# Scheme.net
KiCad netlist of a schematic drawn in EAGLE
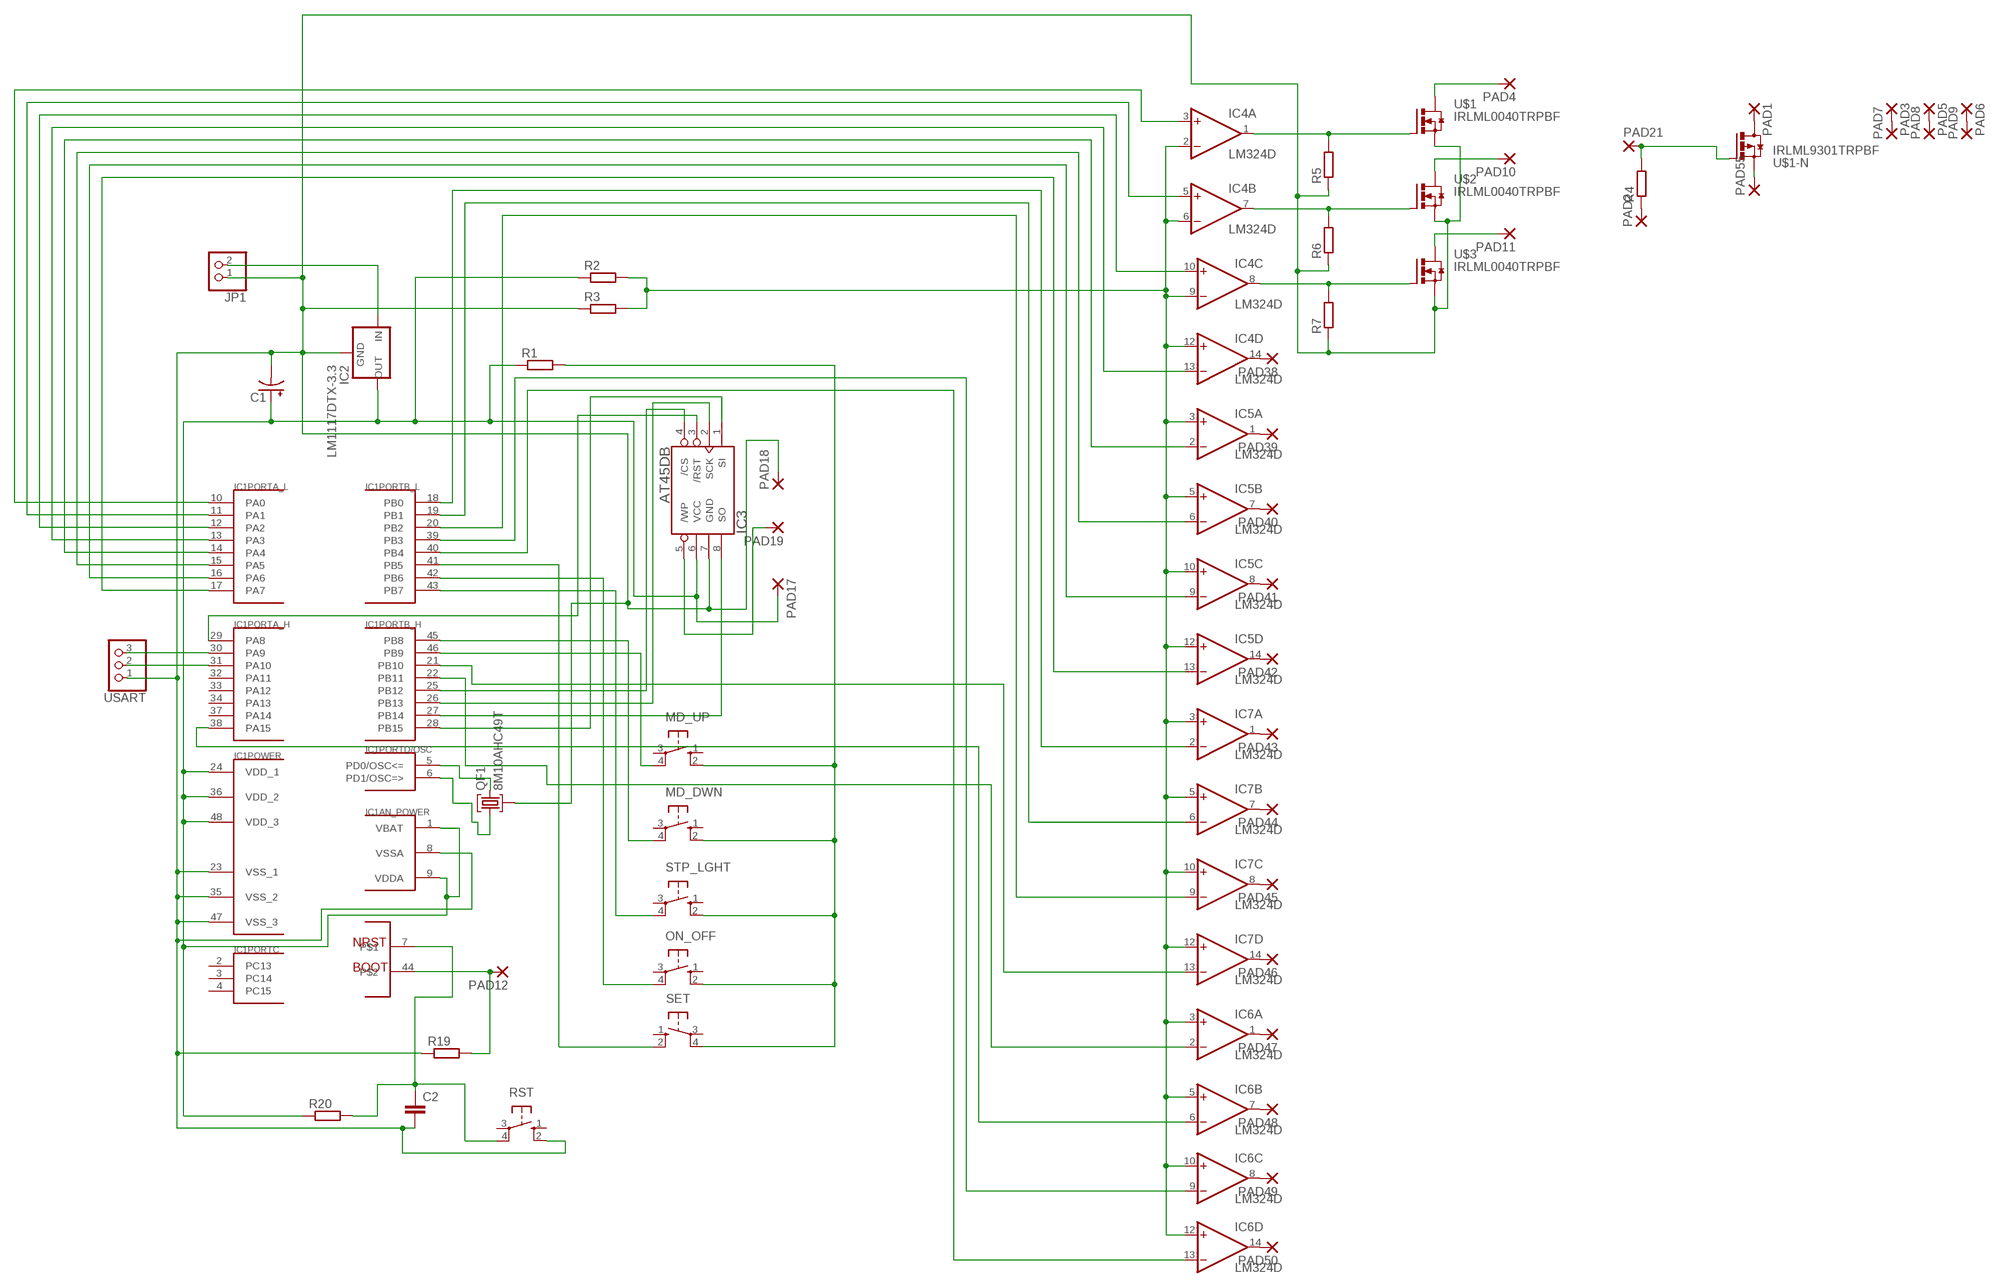
[diagram p0: schematic, sheet 1]

(export (version "E")
  (design (tool "Eeschema 10.0.6"))
  (components
    (comp (ref "C1")
      (value "CPOL-USSMCD")
      (footprint "eagle-import:SMC_D")
      (libsource (lib "eagle-import") (part "CPOL-USSMCD"))
    )
    (comp (ref "C2")
      (value "C-EUC0805")
      (footprint "eagle-import:C0805")
      (libsource (lib "eagle-import") (part "C-EUC0805"))
    )
    (comp (ref "IC1")
      (value "STM32F10XCXT6")
      (footprint "eagle-import:TQFP48")
      (libsource (lib "eagle-import") (part "STM32F10XCXT6"))
    )
    (comp (ref "IC2")
      (value "LM1117DTX-3.3")
      (footprint "eagle-import:TO252")
      (libsource (lib "eagle-import") (part "LM1117DTX-3.3"))
    )
    (comp (ref "IC3")
      (value "AT45DB-S")
      (footprint "eagle-import:SOIC8_208MIL")
      (libsource (lib "eagle-import") (part "AT45DB-S"))
    )
    (comp (ref "IC4")
      (value "LM324D")
      (footprint "eagle-import:SO14")
      (libsource (lib "eagle-import") (part "LM324D"))
    )
    (comp (ref "IC5")
      (value "LM324D")
      (footprint "eagle-import:SO14")
      (libsource (lib "eagle-import") (part "LM324D"))
    )
    (comp (ref "IC6")
      (value "LM324D")
      (footprint "eagle-import:SO14")
      (libsource (lib "eagle-import") (part "LM324D"))
    )
    (comp (ref "IC7")
      (value "LM324D")
      (footprint "eagle-import:SO14")
      (libsource (lib "eagle-import") (part "LM324D"))
    )
    (comp (ref "JP1")
      (value "PINHD-1X2")
      (footprint "eagle-import:1X02")
      (libsource (lib "eagle-import") (part "PINHD-1X2"))
    )
    (comp (ref "MD_DWN")
      (value "40-XX")
      (footprint "eagle-import:B3F-40XX")
      (fields (field (name "MF") "OMRON COMPONENTS USA") (field (name "MPN") "B3F-4000"))
      (libsource (lib "eagle-import") (part "40-XX"))
    )
    (comp (ref "MD_UP")
      (value "40-XX")
      (footprint "eagle-import:B3F-40XX")
      (fields (field (name "MF") "OMRON COMPONENTS USA") (field (name "MPN") "B3F-4000"))
      (libsource (lib "eagle-import") (part "40-XX"))
    )
    (comp (ref "ON_OFF")
      (value "40-XX")
      (footprint "eagle-import:B3F-40XX")
      (fields (field (name "MF") "OMRON COMPONENTS USA") (field (name "MPN") "B3F-4000"))
      (libsource (lib "eagle-import") (part "40-XX"))
    )
    (comp (ref "PAD1")
      (value "SMD2")
      (footprint "eagle-import:SMD1,27-2,54")
      (libsource (lib "eagle-import") (part "SMD2"))
    )
    (comp (ref "PAD2")
      (value "SMD2")
      (footprint "eagle-import:SMD1,27-2,54")
      (libsource (lib "eagle-import") (part "SMD2"))
    )
    (comp (ref "PAD3")
      (value "SMD2")
      (footprint "eagle-import:SMD1,27-2,54")
      (libsource (lib "eagle-import") (part "SMD2"))
    )
    (comp (ref "PAD4")
      (value "SMD2")
      (footprint "eagle-import:SMD1,27-2,54")
      (libsource (lib "eagle-import") (part "SMD2"))
    )
    (comp (ref "PAD5")
      (value "SMD2")
      (footprint "eagle-import:SMD1,27-2,54")
      (libsource (lib "eagle-import") (part "SMD2"))
    )
    (comp (ref "PAD6")
      (value "SMD2")
      (footprint "eagle-import:SMD1,27-2,54")
      (libsource (lib "eagle-import") (part "SMD2"))
    )
    (comp (ref "PAD7")
      (value "SMD2")
      (footprint "eagle-import:SMD1,27-2,54")
      (libsource (lib "eagle-import") (part "SMD2"))
    )
    (comp (ref "PAD8")
      (value "SMD2")
      (footprint "eagle-import:SMD1,27-2,54")
      (libsource (lib "eagle-import") (part "SMD2"))
    )
    (comp (ref "PAD9")
      (value "SMD2")
      (footprint "eagle-import:SMD1,27-2,54")
      (libsource (lib "eagle-import") (part "SMD2"))
    )
    (comp (ref "PAD10")
      (value "SMD2")
      (footprint "eagle-import:SMD1,27-2,54")
      (libsource (lib "eagle-import") (part "SMD2"))
    )
    (comp (ref "PAD11")
      (value "SMD2")
      (footprint "eagle-import:SMD1,27-2,54")
      (libsource (lib "eagle-import") (part "SMD2"))
    )
    (comp (ref "PAD12")
      (value "SMD2")
      (footprint "eagle-import:SMD1,27-2,54")
      (libsource (lib "eagle-import") (part "SMD2"))
    )
    (comp (ref "PAD17")
      (value "SMD2")
      (footprint "eagle-import:SMD1,27-2,54")
      (libsource (lib "eagle-import") (part "SMD2"))
    )
    (comp (ref "PAD18")
      (value "SMD2")
      (footprint "eagle-import:SMD1,27-2,54")
      (libsource (lib "eagle-import") (part "SMD2"))
    )
    (comp (ref "PAD19")
      (value "SMD2")
      (footprint "eagle-import:SMD1,27-2,54")
      (libsource (lib "eagle-import") (part "SMD2"))
    )
    (comp (ref "PAD21")
      (value "SMD2")
      (footprint "eagle-import:SMD1,27-2,54")
      (libsource (lib "eagle-import") (part "SMD2"))
    )
    (comp (ref "PAD38")
      (value "SMD2")
      (footprint "eagle-import:SMD1,27-2,54")
      (libsource (lib "eagle-import") (part "SMD2"))
    )
    (comp (ref "PAD39")
      (value "SMD2")
      (footprint "eagle-import:SMD1,27-2,54")
      (libsource (lib "eagle-import") (part "SMD2"))
    )
    (comp (ref "PAD40")
      (value "SMD2")
      (footprint "eagle-import:SMD1,27-2,54")
      (libsource (lib "eagle-import") (part "SMD2"))
    )
    (comp (ref "PAD41")
      (value "SMD2")
      (footprint "eagle-import:SMD1,27-2,54")
      (libsource (lib "eagle-import") (part "SMD2"))
    )
    (comp (ref "PAD42")
      (value "SMD2")
      (footprint "eagle-import:SMD1,27-2,54")
      (libsource (lib "eagle-import") (part "SMD2"))
    )
    (comp (ref "PAD43")
      (value "SMD2")
      (footprint "eagle-import:SMD1,27-2,54")
      (libsource (lib "eagle-import") (part "SMD2"))
    )
    (comp (ref "PAD44")
      (value "SMD2")
      (footprint "eagle-import:SMD1,27-2,54")
      (libsource (lib "eagle-import") (part "SMD2"))
    )
    (comp (ref "PAD45")
      (value "SMD2")
      (footprint "eagle-import:SMD1,27-2,54")
      (libsource (lib "eagle-import") (part "SMD2"))
    )
    (comp (ref "PAD46")
      (value "SMD2")
      (footprint "eagle-import:SMD1,27-2,54")
      (libsource (lib "eagle-import") (part "SMD2"))
    )
    (comp (ref "PAD47")
      (value "SMD2")
      (footprint "eagle-import:SMD1,27-2,54")
      (libsource (lib "eagle-import") (part "SMD2"))
    )
    (comp (ref "PAD48")
      (value "SMD2")
      (footprint "eagle-import:SMD1,27-2,54")
      (libsource (lib "eagle-import") (part "SMD2"))
    )
    (comp (ref "PAD49")
      (value "SMD2")
      (footprint "eagle-import:SMD1,27-2,54")
      (libsource (lib "eagle-import") (part "SMD2"))
    )
    (comp (ref "PAD50")
      (value "SMD2")
      (footprint "eagle-import:SMD1,27-2,54")
      (libsource (lib "eagle-import") (part "SMD2"))
    )
    (comp (ref "PAD55")
      (value "SMD2")
      (footprint "eagle-import:SMD1,27-2,54")
      (libsource (lib "eagle-import") (part "SMD2"))
    )
    (comp (ref "QF1")
      (value "8M10AHC49T")
      (footprint "eagle-import:HC49U")
      (libsource (lib "eagle-import") (part "8M10AHC49T"))
    )
    (comp (ref "R1")
      (value "R-EU_R1206")
      (footprint "eagle-import:R1206")
      (libsource (lib "eagle-import") (part "R-EU_R1206"))
    )
    (comp (ref "R2")
      (value "R-EU_R1206")
      (footprint "eagle-import:R1206")
      (libsource (lib "eagle-import") (part "R-EU_R1206"))
    )
    (comp (ref "R3")
      (value "R-EU_R1206")
      (footprint "eagle-import:R1206")
      (libsource (lib "eagle-import") (part "R-EU_R1206"))
    )
    (comp (ref "R4")
      (value "R-EU_R1206")
      (footprint "eagle-import:R1206")
      (libsource (lib "eagle-import") (part "R-EU_R1206"))
    )
    (comp (ref "R5")
      (value "R-EU_R1206")
      (footprint "eagle-import:R1206")
      (libsource (lib "eagle-import") (part "R-EU_R1206"))
    )
    (comp (ref "R6")
      (value "R-EU_R1206")
      (footprint "eagle-import:R1206")
      (libsource (lib "eagle-import") (part "R-EU_R1206"))
    )
    (comp (ref "R7")
      (value "R-EU_R1206")
      (footprint "eagle-import:R1206")
      (libsource (lib "eagle-import") (part "R-EU_R1206"))
    )
    (comp (ref "R19")
      (value "R-EU_R1206")
      (footprint "eagle-import:R1206")
      (libsource (lib "eagle-import") (part "R-EU_R1206"))
    )
    (comp (ref "R20")
      (value "R-EU_R1206")
      (footprint "eagle-import:R1206")
      (libsource (lib "eagle-import") (part "R-EU_R1206"))
    )
    (comp (ref "RST")
      (value "40-XX")
      (footprint "eagle-import:B3F-40XX")
      (fields (field (name "MF") "OMRON COMPONENTS USA") (field (name "MPN") "B3F-4000"))
      (libsource (lib "eagle-import") (part "40-XX"))
    )
    (comp (ref "SET")
      (value "40-XX")
      (footprint "eagle-import:B3F-40XX")
      (fields (field (name "MF") "OMRON COMPONENTS USA") (field (name "MPN") "B3F-4000"))
      (libsource (lib "eagle-import") (part "40-XX"))
    )
    (comp (ref "STP_LGHT")
      (value "40-XX")
      (footprint "eagle-import:B3F-40XX")
      (fields (field (name "MF") "OMRON COMPONENTS USA") (field (name "MPN") "B3F-4000"))
      (libsource (lib "eagle-import") (part "40-XX"))
    )
    (comp (ref "U$1")
      (value "IRLML0040TRPBF")
      (footprint "eagle-import:MICRO3")
      (libsource (lib "eagle-import") (part "IRLML0040TRPBF"))
    )
    (comp (ref "U$1-N")
      (value "IRLML9301TRPBF")
      (footprint "eagle-import:MICRO3")
      (libsource (lib "eagle-import") (part "IRLML9301TRPBF"))
    )
    (comp (ref "U$2")
      (value "IRLML0040TRPBF")
      (footprint "eagle-import:MICRO3")
      (libsource (lib "eagle-import") (part "IRLML0040TRPBF"))
    )
    (comp (ref "U$3")
      (value "IRLML0040TRPBF")
      (footprint "eagle-import:MICRO3")
      (libsource (lib "eagle-import") (part "IRLML0040TRPBF"))
    )
    (comp (ref "USART")
      (value "PINHD-1X3")
      (footprint "eagle-import:1X03")
      (libsource (lib "eagle-import") (part "PINHD-1X3"))
    )
  )
  (nets
    (net (code "1") (name "Net-(IC1A-VBAT)") (class "Default")
      (node (ref "C1") (pin "+") (pinfunction "+_+") (pintype "passive"))
      (node (ref "IC1") (pin "1") (pinfunction "VBAT_1") (pintype "power_in"))
      (node (ref "IC1") (pin "24") (pinfunction "VDD_1_24") (pintype "power_in"))
      (node (ref "IC1") (pin "36") (pinfunction "VDD_2_36") (pintype "power_in"))
      (node (ref "IC1") (pin "48") (pinfunction "VDD_3_48") (pintype "power_in"))
      (node (ref "IC1") (pin "9") (pinfunction "VDDA_9") (pintype "power_in"))
      (node (ref "IC2") (pin "TAB") (pinfunction "OUT_TAB") (pintype "passive"))
      (node (ref "IC3") (pin "6") (pinfunction "VCC_6") (pintype "power_in"))
      (node (ref "PAD17") (pin "1") (pinfunction "P_1") (pintype "passive"))
      (node (ref "R1") (pin "1") (pinfunction "1_1") (pintype "passive"))
      (node (ref "R2") (pin "1") (pinfunction "1_1") (pintype "passive"))
      (node (ref "R20") (pin "1") (pinfunction "1_1") (pintype "passive"))
    )
    (net (code "2") (name "Net-(IC1A-VSSA)") (class "Default")
      (node (ref "C1") (pin "-") (pinfunction "-_-") (pintype "passive"))
      (node (ref "C2") (pin "2") (pinfunction "2_2") (pintype "passive"))
      (node (ref "IC1") (pin "23") (pinfunction "VSS_1_23") (pintype "power_in"))
      (node (ref "IC1") (pin "35") (pinfunction "VSS_2_35") (pintype "power_in"))
      (node (ref "IC1") (pin "47") (pinfunction "VSS_3_47") (pintype "power_in"))
      (node (ref "IC1") (pin "8") (pinfunction "VSSA_8") (pintype "power_in"))
      (node (ref "IC2") (pin "1") (pinfunction "GND_1") (pintype "input"))
      (node (ref "IC3") (pin "7") (pinfunction "GND_7") (pintype "power_in"))
      (node (ref "JP1") (pin "1") (pinfunction "1_1") (pintype "passive"))
      (node (ref "PAD18") (pin "1") (pinfunction "P_1") (pintype "passive"))
      (node (ref "QF1") (pin "2") (pinfunction "2_2") (pintype "passive"))
      (node (ref "R19") (pin "1") (pinfunction "1_1") (pintype "passive"))
      (node (ref "R3") (pin "1") (pinfunction "1_1") (pintype "passive"))
      (node (ref "R5") (pin "1") (pinfunction "1_1") (pintype "passive"))
      (node (ref "R6") (pin "1") (pinfunction "1_1") (pintype "passive"))
      (node (ref "R7") (pin "1") (pinfunction "1_1") (pintype "passive"))
      (node (ref "RST") (pin "2") (pinfunction "S1_2") (pintype "passive"))
      (node (ref "U$1") (pin "2") (pinfunction "S_2") (pintype "passive"))
      (node (ref "U$2") (pin "2") (pinfunction "S_2") (pintype "passive"))
      (node (ref "U$3") (pin "2") (pinfunction "S_2") (pintype "passive"))
      (node (ref "USART") (pin "1") (pinfunction "1_1") (pintype "passive"))
    )
    (net (code "3") (name "Net-(IC1B-P$1)") (class "Default")
      (node (ref "C2") (pin "1") (pinfunction "1_1") (pintype "passive"))
      (node (ref "IC1") (pin "7") (pinfunction "P$1_7") (pintype "bidirectional"))
      (node (ref "R20") (pin "2") (pinfunction "2_2") (pintype "passive"))
      (node (ref "RST") (pin "4") (pinfunction "P1_4") (pintype "passive"))
    )
    (net (code "4") (name "Net-(IC1B-P$2)") (class "Default")
      (node (ref "IC1") (pin "44") (pinfunction "P$2_44") (pintype "bidirectional"))
      (node (ref "PAD12") (pin "1") (pinfunction "P_1") (pintype "passive"))
      (node (ref "R19") (pin "2") (pinfunction "2_2") (pintype "passive"))
    )
    (net (code "5") (name "Net-(IC1C-PA8)") (class "Default")
      (node (ref "IC1") (pin "29") (pinfunction "PA8_29") (pintype "bidirectional"))
      (node (ref "IC3") (pin "3") (pinfunction "/RST_3") (pintype "input"))
    )
    (net (code "6") (name "Net-(IC1C-PA9)") (class "Default")
      (node (ref "IC1") (pin "30") (pinfunction "PA9_30") (pintype "bidirectional"))
      (node (ref "USART") (pin "3") (pinfunction "3_3") (pintype "passive"))
    )
    (net (code "7") (name "Net-(IC1C-PA10)") (class "Default")
      (node (ref "IC1") (pin "31") (pinfunction "PA10_31") (pintype "bidirectional"))
      (node (ref "USART") (pin "2") (pinfunction "2_2") (pintype "passive"))
    )
    (net (code "8") (name "Net-(IC1C-PA15)") (class "Default")
      (node (ref "IC1") (pin "38") (pinfunction "PA15_38") (pintype "bidirectional"))
      (node (ref "IC6") (pin "6") (pinfunction "-IN_6") (pintype "input"))
    )
    (net (code "9") (name "Net-(IC1D-PA0)") (class "Default")
      (node (ref "IC1") (pin "10") (pinfunction "PA0_10") (pintype "bidirectional"))
      (node (ref "IC4") (pin "3") (pinfunction "+IN_3") (pintype "input"))
    )
    (net (code "10") (name "Net-(IC1D-PA1)") (class "Default")
      (node (ref "IC1") (pin "11") (pinfunction "PA1_11") (pintype "bidirectional"))
      (node (ref "IC4") (pin "5") (pinfunction "+IN_5") (pintype "input"))
    )
    (net (code "11") (name "Net-(IC1D-PA2)") (class "Default")
      (node (ref "IC1") (pin "12") (pinfunction "PA2_12") (pintype "bidirectional"))
      (node (ref "IC4") (pin "10") (pinfunction "+IN_10") (pintype "input"))
    )
    (net (code "12") (name "Net-(IC1D-PA3)") (class "Default")
      (node (ref "IC1") (pin "13") (pinfunction "PA3_13") (pintype "bidirectional"))
      (node (ref "IC4") (pin "13") (pinfunction "-IN_13") (pintype "input"))
    )
    (net (code "13") (name "Net-(IC1D-PA4)") (class "Default")
      (node (ref "IC1") (pin "14") (pinfunction "PA4_14") (pintype "bidirectional"))
      (node (ref "IC5") (pin "2") (pinfunction "-IN_2") (pintype "input"))
    )
    (net (code "14") (name "Net-(IC1D-PA5)") (class "Default")
      (node (ref "IC1") (pin "15") (pinfunction "PA5_15") (pintype "bidirectional"))
      (node (ref "IC5") (pin "6") (pinfunction "-IN_6") (pintype "input"))
    )
    (net (code "15") (name "Net-(IC1D-PA6)") (class "Default")
      (node (ref "IC1") (pin "16") (pinfunction "PA6_16") (pintype "bidirectional"))
      (node (ref "IC5") (pin "9") (pinfunction "-IN_9") (pintype "input"))
    )
    (net (code "16") (name "Net-(IC1D-PA7)") (class "Default")
      (node (ref "IC1") (pin "17") (pinfunction "PA7_17") (pintype "bidirectional"))
      (node (ref "IC5") (pin "13") (pinfunction "-IN_13") (pintype "input"))
    )
    (net (code "17") (name "Net-(IC1E-PB8)") (class "Default")
      (node (ref "IC1") (pin "45") (pinfunction "PB8_45") (pintype "bidirectional"))
      (node (ref "MD_DWN") (pin "4") (pinfunction "P1_4") (pintype "passive"))
    )
    (net (code "18") (name "Net-(IC1E-PB9)") (class "Default")
      (node (ref "IC1") (pin "46") (pinfunction "PB9_46") (pintype "bidirectional"))
      (node (ref "MD_UP") (pin "4") (pinfunction "P1_4") (pintype "passive"))
    )
    (net (code "19") (name "Net-(IC1E-PB10)") (class "Default")
      (node (ref "IC1") (pin "21") (pinfunction "PB10_21") (pintype "bidirectional"))
      (node (ref "IC7") (pin "13") (pinfunction "-IN_13") (pintype "input"))
    )
    (net (code "20") (name "Net-(IC1E-PB11)") (class "Default")
      (node (ref "IC1") (pin "22") (pinfunction "PB11_22") (pintype "bidirectional"))
      (node (ref "IC6") (pin "2") (pinfunction "-IN_2") (pintype "input"))
    )
    (net (code "21") (name "Net-(IC1E-PB12)") (class "Default")
      (node (ref "IC1") (pin "25") (pinfunction "PB12_25") (pintype "bidirectional"))
      (node (ref "IC3") (pin "4") (pinfunction "/CS_4") (pintype "input"))
    )
    (net (code "22") (name "Net-(IC1E-PB13)") (class "Default")
      (node (ref "IC1") (pin "26") (pinfunction "PB13_26") (pintype "bidirectional"))
      (node (ref "IC3") (pin "2") (pinfunction "SCK_2") (pintype "input"))
    )
    (net (code "23") (name "Net-(IC1E-PB14)") (class "Default")
      (node (ref "IC1") (pin "27") (pinfunction "PB14_27") (pintype "bidirectional"))
      (node (ref "IC3") (pin "8") (pinfunction "SO_8") (pintype "output"))
    )
    (net (code "24") (name "Net-(IC1E-PB15)") (class "Default")
      (node (ref "IC1") (pin "28") (pinfunction "PB15_28") (pintype "bidirectional"))
      (node (ref "IC3") (pin "1") (pinfunction "SI_1") (pintype "input"))
    )
    (net (code "25") (name "Net-(IC1F-PB0)") (class "Default")
      (node (ref "IC1") (pin "18") (pinfunction "PB0_18") (pintype "bidirectional"))
      (node (ref "IC7") (pin "2") (pinfunction "-IN_2") (pintype "input"))
    )
    (net (code "26") (name "Net-(IC1F-PB1)") (class "Default")
      (node (ref "IC1") (pin "19") (pinfunction "PB1_19") (pintype "bidirectional"))
      (node (ref "IC7") (pin "6") (pinfunction "-IN_6") (pintype "input"))
    )
    (net (code "27") (name "Net-(IC1F-PB2)") (class "Default")
      (node (ref "IC1") (pin "20") (pinfunction "PB2_20") (pintype "bidirectional"))
      (node (ref "IC7") (pin "9") (pinfunction "-IN_9") (pintype "input"))
    )
    (net (code "28") (name "Net-(IC1F-PB3)") (class "Default")
      (node (ref "IC1") (pin "39") (pinfunction "PB3_39") (pintype "bidirectional"))
      (node (ref "IC6") (pin "9") (pinfunction "-IN_9") (pintype "input"))
    )
    (net (code "29") (name "Net-(IC1F-PB4)") (class "Default")
      (node (ref "IC1") (pin "40") (pinfunction "PB4_40") (pintype "bidirectional"))
      (node (ref "IC6") (pin "13") (pinfunction "-IN_13") (pintype "input"))
    )
    (net (code "30") (name "Net-(IC1F-PB5)") (class "Default")
      (node (ref "IC1") (pin "41") (pinfunction "PB5_41") (pintype "bidirectional"))
      (node (ref "SET") (pin "2") (pinfunction "S1_2") (pintype "passive"))
    )
    (net (code "31") (name "Net-(IC1F-PB6)") (class "Default")
      (node (ref "IC1") (pin "42") (pinfunction "PB6_42") (pintype "bidirectional"))
      (node (ref "ON_OFF") (pin "4") (pinfunction "P1_4") (pintype "passive"))
    )
    (net (code "32") (name "Net-(IC1F-PB7)") (class "Default")
      (node (ref "IC1") (pin "43") (pinfunction "PB7_43") (pintype "bidirectional"))
      (node (ref "STP_LGHT") (pin "4") (pinfunction "P1_4") (pintype "passive"))
    )
    (net (code "33") (name "Net-(IC1H-PD0{slash}OSC<=)") (class "Default")
      (node (ref "IC1") (pin "5") (pinfunction "PD0/OSC<=_5") (pintype "bidirectional"))
      (node (ref "QF1") (pin "3") (pinfunction "3_3") (pintype "passive"))
    )
    (net (code "34") (name "Net-(IC1H-PD1{slash}OSC=>)") (class "Default")
      (node (ref "IC1") (pin "6") (pinfunction "PD1/OSC=>_6") (pintype "bidirectional"))
      (node (ref "QF1") (pin "1") (pinfunction "1_1") (pintype "passive"))
    )
    (net (code "35") (name "Net-(IC2-IN)") (class "Default")
      (node (ref "IC2") (pin "2") (pinfunction "IN_2") (pintype "input"))
      (node (ref "JP1") (pin "2") (pinfunction "2_2") (pintype "passive"))
    )
    (net (code "36") (name "Net-(IC3-{slash}WP)") (class "Default")
      (node (ref "IC3") (pin "5") (pinfunction "/WP_5") (pintype "input"))
      (node (ref "PAD19") (pin "1") (pinfunction "P_1") (pintype "passive"))
    )
    (net (code "37") (name "Net-(IC4A--IN)") (class "Default")
      (node (ref "IC4") (pin "12") (pinfunction "+IN_12") (pintype "input"))
      (node (ref "IC4") (pin "2") (pinfunction "-IN_2") (pintype "input"))
      (node (ref "IC4") (pin "6") (pinfunction "-IN_6") (pintype "input"))
      (node (ref "IC4") (pin "9") (pinfunction "-IN_9") (pintype "input"))
      (node (ref "IC5") (pin "10") (pinfunction "+IN_10") (pintype "input"))
      (node (ref "IC5") (pin "12") (pinfunction "+IN_12") (pintype "input"))
      (node (ref "IC5") (pin "3") (pinfunction "+IN_3") (pintype "input"))
      (node (ref "IC5") (pin "5") (pinfunction "+IN_5") (pintype "input"))
      (node (ref "IC6") (pin "10") (pinfunction "+IN_10") (pintype "input"))
      (node (ref "IC6") (pin "12") (pinfunction "+IN_12") (pintype "input"))
      (node (ref "IC6") (pin "3") (pinfunction "+IN_3") (pintype "input"))
      (node (ref "IC6") (pin "5") (pinfunction "+IN_5") (pintype "input"))
      (node (ref "IC7") (pin "10") (pinfunction "+IN_10") (pintype "input"))
      (node (ref "IC7") (pin "12") (pinfunction "+IN_12") (pintype "input"))
      (node (ref "IC7") (pin "3") (pinfunction "+IN_3") (pintype "input"))
      (node (ref "IC7") (pin "5") (pinfunction "+IN_5") (pintype "input"))
      (node (ref "R2") (pin "2") (pinfunction "2_2") (pintype "passive"))
      (node (ref "R3") (pin "2") (pinfunction "2_2") (pintype "passive"))
    )
    (net (code "38") (name "Net-(IC4A-OUT)") (class "Default")
      (node (ref "IC4") (pin "1") (pinfunction "OUT_1") (pintype "output"))
      (node (ref "R5") (pin "2") (pinfunction "2_2") (pintype "passive"))
      (node (ref "U$1") (pin "1") (pinfunction "G_1") (pintype "passive"))
    )
    (net (code "39") (name "Net-(IC4B-OUT)") (class "Default")
      (node (ref "IC4") (pin "7") (pinfunction "OUT_7") (pintype "output"))
      (node (ref "R6") (pin "2") (pinfunction "2_2") (pintype "passive"))
      (node (ref "U$2") (pin "1") (pinfunction "G_1") (pintype "passive"))
    )
    (net (code "40") (name "Net-(IC4C-OUT)") (class "Default")
      (node (ref "IC4") (pin "8") (pinfunction "OUT_8") (pintype "output"))
      (node (ref "R7") (pin "2") (pinfunction "2_2") (pintype "passive"))
      (node (ref "U$3") (pin "1") (pinfunction "G_1") (pintype "passive"))
    )
    (net (code "41") (name "Net-(IC4D-OUT)") (class "Default")
      (node (ref "IC4") (pin "14") (pinfunction "OUT_14") (pintype "output"))
      (node (ref "PAD38") (pin "1") (pinfunction "P_1") (pintype "passive"))
    )
    (net (code "42") (name "Net-(IC5A-OUT)") (class "Default")
      (node (ref "IC5") (pin "1") (pinfunction "OUT_1") (pintype "output"))
      (node (ref "PAD39") (pin "1") (pinfunction "P_1") (pintype "passive"))
    )
    (net (code "43") (name "Net-(IC5B-OUT)") (class "Default")
      (node (ref "IC5") (pin "7") (pinfunction "OUT_7") (pintype "output"))
      (node (ref "PAD40") (pin "1") (pinfunction "P_1") (pintype "passive"))
    )
    (net (code "44") (name "Net-(IC5C-OUT)") (class "Default")
      (node (ref "IC5") (pin "8") (pinfunction "OUT_8") (pintype "output"))
      (node (ref "PAD41") (pin "1") (pinfunction "P_1") (pintype "passive"))
    )
    (net (code "45") (name "Net-(IC5D-OUT)") (class "Default")
      (node (ref "IC5") (pin "14") (pinfunction "OUT_14") (pintype "output"))
      (node (ref "PAD42") (pin "1") (pinfunction "P_1") (pintype "passive"))
    )
    (net (code "46") (name "Net-(IC6A-OUT)") (class "Default")
      (node (ref "IC6") (pin "1") (pinfunction "OUT_1") (pintype "output"))
      (node (ref "PAD47") (pin "1") (pinfunction "P_1") (pintype "passive"))
    )
    (net (code "47") (name "Net-(IC6B-OUT)") (class "Default")
      (node (ref "IC6") (pin "7") (pinfunction "OUT_7") (pintype "output"))
      (node (ref "PAD48") (pin "1") (pinfunction "P_1") (pintype "passive"))
    )
    (net (code "48") (name "Net-(IC6C-OUT)") (class "Default")
      (node (ref "IC6") (pin "8") (pinfunction "OUT_8") (pintype "output"))
      (node (ref "PAD49") (pin "1") (pinfunction "P_1") (pintype "passive"))
    )
    (net (code "49") (name "Net-(IC6D-OUT)") (class "Default")
      (node (ref "IC6") (pin "14") (pinfunction "OUT_14") (pintype "output"))
      (node (ref "PAD50") (pin "1") (pinfunction "P_1") (pintype "passive"))
    )
    (net (code "50") (name "Net-(IC7A-OUT)") (class "Default")
      (node (ref "IC7") (pin "1") (pinfunction "OUT_1") (pintype "output"))
      (node (ref "PAD43") (pin "1") (pinfunction "P_1") (pintype "passive"))
    )
    (net (code "51") (name "Net-(IC7B-OUT)") (class "Default")
      (node (ref "IC7") (pin "7") (pinfunction "OUT_7") (pintype "output"))
      (node (ref "PAD44") (pin "1") (pinfunction "P_1") (pintype "passive"))
    )
    (net (code "52") (name "Net-(IC7C-OUT)") (class "Default")
      (node (ref "IC7") (pin "8") (pinfunction "OUT_8") (pintype "output"))
      (node (ref "PAD45") (pin "1") (pinfunction "P_1") (pintype "passive"))
    )
    (net (code "53") (name "Net-(IC7D-OUT)") (class "Default")
      (node (ref "IC7") (pin "14") (pinfunction "OUT_14") (pintype "output"))
      (node (ref "PAD46") (pin "1") (pinfunction "P_1") (pintype "passive"))
    )
    (net (code "54") (name "Net-(MD_DWN-S1)") (class "Default")
      (node (ref "MD_DWN") (pin "2") (pinfunction "S1_2") (pintype "passive"))
      (node (ref "MD_UP") (pin "2") (pinfunction "S1_2") (pintype "passive"))
      (node (ref "ON_OFF") (pin "2") (pinfunction "S1_2") (pintype "passive"))
      (node (ref "R1") (pin "2") (pinfunction "2_2") (pintype "passive"))
      (node (ref "SET") (pin "4") (pinfunction "P1_4") (pintype "passive"))
      (node (ref "STP_LGHT") (pin "2") (pinfunction "S1_2") (pintype "passive"))
    )
    (net (code "55") (name "Net-(PAD1-P)") (class "Default")
      (node (ref "PAD1") (pin "1") (pinfunction "P_1") (pintype "passive"))
      (node (ref "U$1-N") (pin "3") (pinfunction "D_3") (pintype "passive"))
    )
    (net (code "56") (name "Net-(PAD2-P)") (class "Default")
      (node (ref "PAD2") (pin "1") (pinfunction "P_1") (pintype "passive"))
      (node (ref "R4") (pin "1") (pinfunction "1_1") (pintype "passive"))
    )
    (net (code "57") (name "Net-(PAD3-P)") (class "Default")
      (node (ref "PAD3") (pin "1") (pinfunction "P_1") (pintype "passive"))
      (node (ref "PAD7") (pin "1") (pinfunction "P_1") (pintype "passive"))
    )
    (net (code "58") (name "Net-(PAD4-P)") (class "Default")
      (node (ref "PAD4") (pin "1") (pinfunction "P_1") (pintype "passive"))
      (node (ref "U$1") (pin "3") (pinfunction "D_3") (pintype "passive"))
    )
    (net (code "59") (name "Net-(PAD5-P)") (class "Default")
      (node (ref "PAD5") (pin "1") (pinfunction "P_1") (pintype "passive"))
      (node (ref "PAD8") (pin "1") (pinfunction "P_1") (pintype "passive"))
    )
    (net (code "60") (name "Net-(PAD6-P)") (class "Default")
      (node (ref "PAD6") (pin "1") (pinfunction "P_1") (pintype "passive"))
      (node (ref "PAD9") (pin "1") (pinfunction "P_1") (pintype "passive"))
    )
    (net (code "61") (name "Net-(PAD10-P)") (class "Default")
      (node (ref "PAD10") (pin "1") (pinfunction "P_1") (pintype "passive"))
      (node (ref "U$2") (pin "3") (pinfunction "D_3") (pintype "passive"))
    )
    (net (code "62") (name "Net-(PAD11-P)") (class "Default")
      (node (ref "PAD11") (pin "1") (pinfunction "P_1") (pintype "passive"))
      (node (ref "U$3") (pin "3") (pinfunction "D_3") (pintype "passive"))
    )
    (net (code "63") (name "Net-(PAD21-P)") (class "Default")
      (node (ref "PAD21") (pin "1") (pinfunction "P_1") (pintype "passive"))
      (node (ref "R4") (pin "2") (pinfunction "2_2") (pintype "passive"))
      (node (ref "U$1-N") (pin "1") (pinfunction "G_1") (pintype "passive"))
    )
    (net (code "64") (name "Net-(PAD55-P)") (class "Default")
      (node (ref "PAD55") (pin "1") (pinfunction "P_1") (pintype "passive"))
      (node (ref "U$1-N") (pin "2") (pinfunction "S_2") (pintype "passive"))
    )
    (net (code "65") (name "unconnected-(IC1C-PA11-Pad32)") (class "Default")
      (node (ref "IC1") (pin "32") (pinfunction "PA11_32") (pintype "bidirectional"))
    )
    (net (code "66") (name "unconnected-(IC1C-PA12-Pad33)") (class "Default")
      (node (ref "IC1") (pin "33") (pinfunction "PA12_33") (pintype "bidirectional"))
    )
    (net (code "67") (name "unconnected-(IC1C-PA13-Pad34)") (class "Default")
      (node (ref "IC1") (pin "34") (pinfunction "PA13_34") (pintype "bidirectional"))
    )
    (net (code "68") (name "unconnected-(IC1C-PA14-Pad37)") (class "Default")
      (node (ref "IC1") (pin "37") (pinfunction "PA14_37") (pintype "bidirectional"))
    )
    (net (code "69") (name "unconnected-(IC1G-PC13-Pad2)") (class "Default")
      (node (ref "IC1") (pin "2") (pinfunction "PC13_2") (pintype "bidirectional"))
    )
    (net (code "70") (name "unconnected-(IC1G-PC14-Pad3)") (class "Default")
      (node (ref "IC1") (pin "3") (pinfunction "PC14_3") (pintype "bidirectional"))
    )
    (net (code "71") (name "unconnected-(IC1G-PC15-Pad4)") (class "Default")
      (node (ref "IC1") (pin "4") (pinfunction "PC15_4") (pintype "bidirectional"))
    )
    (net (code "72") (name "unconnected-(MD_DWN-P-Pad3)") (class "Default")
      (node (ref "MD_DWN") (pin "3") (pinfunction "P_3") (pintype "passive"))
    )
    (net (code "73") (name "unconnected-(MD_DWN-S-Pad1)") (class "Default")
      (node (ref "MD_DWN") (pin "1") (pinfunction "S_1") (pintype "passive"))
    )
    (net (code "74") (name "unconnected-(MD_UP-P-Pad3)") (class "Default")
      (node (ref "MD_UP") (pin "3") (pinfunction "P_3") (pintype "passive"))
    )
    (net (code "75") (name "unconnected-(MD_UP-S-Pad1)") (class "Default")
      (node (ref "MD_UP") (pin "1") (pinfunction "S_1") (pintype "passive"))
    )
    (net (code "76") (name "unconnected-(ON_OFF-P-Pad3)") (class "Default")
      (node (ref "ON_OFF") (pin "3") (pinfunction "P_3") (pintype "passive"))
    )
    (net (code "77") (name "unconnected-(ON_OFF-S-Pad1)") (class "Default")
      (node (ref "ON_OFF") (pin "1") (pinfunction "S_1") (pintype "passive"))
    )
    (net (code "78") (name "unconnected-(RST-P-Pad3)") (class "Default")
      (node (ref "RST") (pin "3") (pinfunction "P_3") (pintype "passive"))
    )
    (net (code "79") (name "unconnected-(RST-S-Pad1)") (class "Default")
      (node (ref "RST") (pin "1") (pinfunction "S_1") (pintype "passive"))
    )
    (net (code "80") (name "unconnected-(SET-P-Pad3)") (class "Default")
      (node (ref "SET") (pin "3") (pinfunction "P_3") (pintype "passive"))
    )
    (net (code "81") (name "unconnected-(SET-S-Pad1)") (class "Default")
      (node (ref "SET") (pin "1") (pinfunction "S_1") (pintype "passive"))
    )
    (net (code "82") (name "unconnected-(STP_LGHT-P-Pad3)") (class "Default")
      (node (ref "STP_LGHT") (pin "3") (pinfunction "P_3") (pintype "passive"))
    )
    (net (code "83") (name "unconnected-(STP_LGHT-S-Pad1)") (class "Default")
      (node (ref "STP_LGHT") (pin "1") (pinfunction "S_1") (pintype "passive"))
    )
  )
)
